# lcd_octopus_t2313.net
KiCad netlist of a schematic drawn in EAGLE
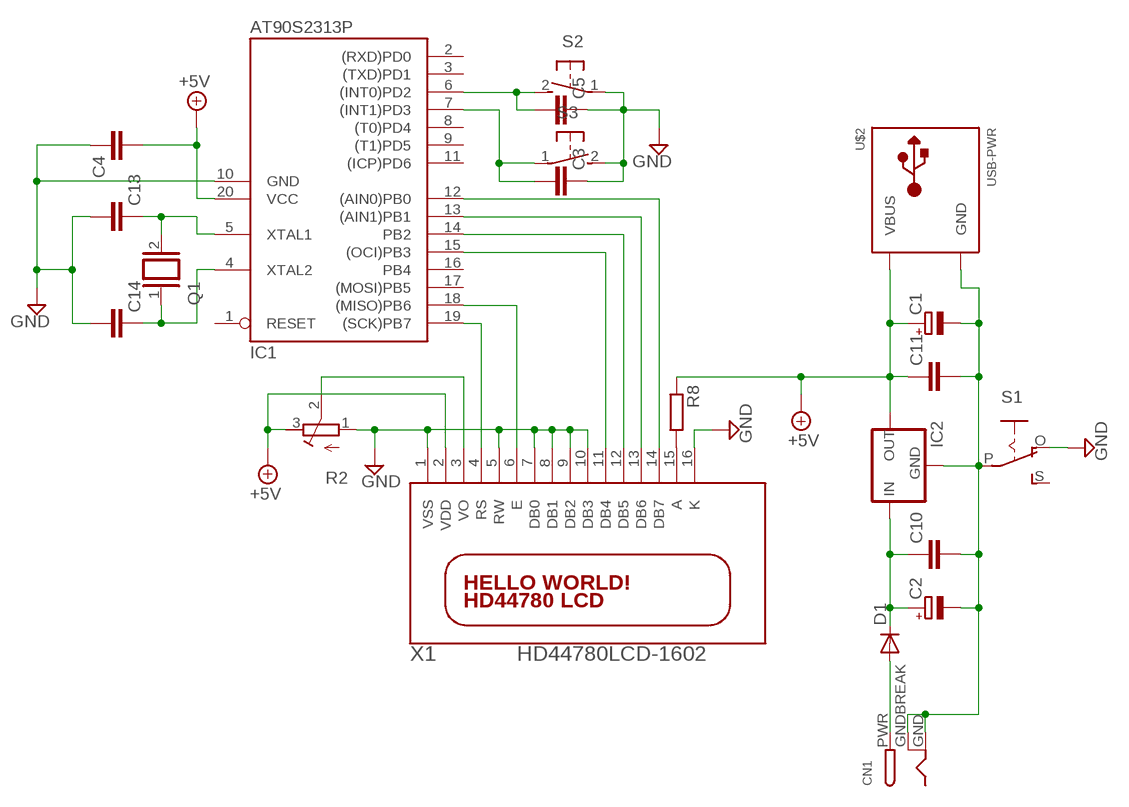
[diagram p0: schematic, sheet 1]

(export (version "E")
  (design (tool "Eeschema 10.0.6"))
  (components
    (comp (ref "C1")
      (value "CPOL-EUTT2D5L")
      (footprint "eagle-import:TT2D5L")
      (libsource (lib "eagle-import") (part "CPOL-EUTT2D5L"))
    )
    (comp (ref "C2")
      (value "CPOL-EUTT2D5L")
      (footprint "eagle-import:TT2D5L")
      (libsource (lib "eagle-import") (part "CPOL-EUTT2D5L"))
    )
    (comp (ref "C3")
      (value "C-EU025-025X050")
      (footprint "eagle-import:C025-025X050")
      (libsource (lib "eagle-import") (part "C-EU025-025X050"))
    )
    (comp (ref "C4")
      (value "C-EU025-025X050")
      (footprint "eagle-import:C025-025X050")
      (libsource (lib "eagle-import") (part "C-EU025-025X050"))
    )
    (comp (ref "C5")
      (value "C-EU025-025X050")
      (footprint "eagle-import:C025-025X050")
      (libsource (lib "eagle-import") (part "C-EU025-025X050"))
    )
    (comp (ref "C10")
      (value "C-EU025-025X050")
      (footprint "eagle-import:C025-025X050")
      (libsource (lib "eagle-import") (part "C-EU025-025X050"))
    )
    (comp (ref "C11")
      (value "C-EU025-025X050")
      (footprint "eagle-import:C025-025X050")
      (libsource (lib "eagle-import") (part "C-EU025-025X050"))
    )
    (comp (ref "C13")
      (value "C-EU025-025X050")
      (footprint "eagle-import:C025-025X050")
      (libsource (lib "eagle-import") (part "C-EU025-025X050"))
    )
    (comp (ref "C14")
      (value "C-EU025-025X050")
      (footprint "eagle-import:C025-025X050")
      (libsource (lib "eagle-import") (part "C-EU025-025X050"))
    )
    (comp (ref "CN1")
      (value "DCBARRELPTH")
      (footprint "eagle-import:DCJACK_2MM_PTH")
      (libsource (lib "eagle-import") (part "DCBARRELPTH"))
    )
    (comp (ref "D1")
      (value "DIODE-D-2.5")
      (footprint "eagle-import:D-2.5")
      (libsource (lib "eagle-import") (part "DIODE-D-2.5"))
    )
    (comp (ref "IC1")
      (value "AT90S2313P")
      (footprint "eagle-import:DIL20")
      (libsource (lib "eagle-import") (part "AT90S2313P"))
    )
    (comp (ref "IC2")
      (value "78XX_V")
      (footprint "eagle-import:78XXV")
      (libsource (lib "eagle-import") (part "78XX_V"))
    )
    (comp (ref "Q1")
      (value "XTAL/S")
      (footprint "eagle-import:QS")
      (libsource (lib "eagle-import") (part "XTAL/S"))
    )
    (comp (ref "R2")
      (value "R-TRIMM3339P")
      (footprint "eagle-import:RTRIM3339P")
      (libsource (lib "eagle-import") (part "R-TRIMM3339P"))
    )
    (comp (ref "R8")
      (value "R-EU_0207/10")
      (footprint "eagle-import:0207_10")
      (libsource (lib "eagle-import") (part "R-EU_0207/10"))
    )
    (comp (ref "S1")
      (value "EG1218S")
      (footprint "eagle-import:EG1218")
      (libsource (lib "eagle-import") (part "EG1218S"))
    )
    (comp (ref "S2")
      (value "31-XX")
      (footprint "eagle-import:B3F-31XX")
      (libsource (lib "eagle-import") (part "31-XX"))
    )
    (comp (ref "S3")
      (value "31-XX")
      (footprint "eagle-import:B3F-31XX")
      (libsource (lib "eagle-import") (part "31-XX"))
    )
    (comp (ref "U$2")
      (value "USB-PWR")
      (footprint "eagle-import:USB-MINIB-THM-MOLEX-PWRONLY")
      (libsource (lib "eagle-import") (part "USB-PWR"))
    )
    (comp (ref "X1")
      (value "HD44780LCD-1602")
      (footprint "eagle-import:LCD1602")
      (libsource (lib "eagle-import") (part "HD44780LCD-1602"))
    )
  )
  (nets
    (net (code "1") (name "+5V") (class "Default")
      (node (ref "C1") (pin "+") (pinfunction "+_+") (pintype "passive"))
      (node (ref "C11") (pin "1") (pinfunction "1_1") (pintype "passive"))
      (node (ref "C4") (pin "2") (pinfunction "2_2") (pintype "passive"))
      (node (ref "IC1") (pin "20") (pinfunction "VCC_20") (pintype "power_in"))
      (node (ref "IC2") (pin "OUT") (pinfunction "OUT_OUT") (pintype "passive"))
      (node (ref "R2") (pin "3") (pinfunction "E_3") (pintype "passive"))
      (node (ref "R8") (pin "1") (pinfunction "1_1") (pintype "passive"))
      (node (ref "U$2") (pin "VBUS") (pinfunction "VBUS_VBUS") (pintype "power_in"))
      (node (ref "X1") (pin "2") (pinfunction "VDD_2") (pintype "power_in"))
    )
    (net (code "2") (name "GND") (class "Default")
      (node (ref "C13") (pin "2") (pinfunction "2_2") (pintype "passive"))
      (node (ref "C14") (pin "2") (pinfunction "2_2") (pintype "passive"))
      (node (ref "C3") (pin "1") (pinfunction "1_1") (pintype "passive"))
      (node (ref "C4") (pin "1") (pinfunction "1_1") (pintype "passive"))
      (node (ref "C5") (pin "1") (pinfunction "1_1") (pintype "passive"))
      (node (ref "IC1") (pin "10") (pinfunction "GND_10") (pintype "power_in"))
      (node (ref "R2") (pin "1") (pinfunction "A_1") (pintype "passive"))
      (node (ref "S1") (pin "O") (pinfunction "O_O") (pintype "passive"))
      (node (ref "S2") (pin "1") (pinfunction "P_1") (pintype "passive"))
      (node (ref "S3") (pin "2") (pinfunction "S_2") (pintype "passive"))
      (node (ref "X1") (pin "1") (pinfunction "VSS_1") (pintype "power_in"))
      (node (ref "X1") (pin "10") (pinfunction "DB3_10") (pintype "bidirectional"))
      (node (ref "X1") (pin "16") (pinfunction "K_16") (pintype "input"))
      (node (ref "X1") (pin "5") (pinfunction "RW_5") (pintype "input"))
      (node (ref "X1") (pin "7") (pinfunction "DB0_7") (pintype "bidirectional"))
      (node (ref "X1") (pin "8") (pinfunction "DB1_8") (pintype "bidirectional"))
      (node (ref "X1") (pin "9") (pinfunction "DB2_9") (pintype "bidirectional"))
    )
    (net (code "3") (name "Net-(C1-Pad-)") (class "Default")
      (node (ref "C1") (pin "-") (pinfunction "-_-") (pintype "passive"))
      (node (ref "C10") (pin "2") (pinfunction "2_2") (pintype "passive"))
      (node (ref "C11") (pin "2") (pinfunction "2_2") (pintype "passive"))
      (node (ref "C2") (pin "-") (pinfunction "-_-") (pintype "passive"))
      (node (ref "CN1") (pin "GND") (pinfunction "GND_GND") (pintype "power_in"))
      (node (ref "CN1") (pin "GNDBREAK") (pinfunction "GNDBREAK_GNDBREAK") (pintype "power_in"))
      (node (ref "IC2") (pin "GND") (pinfunction "GND_GND") (pintype "input"))
      (node (ref "S1") (pin "P") (pinfunction "P_P") (pintype "passive"))
      (node (ref "U$2") (pin "GND") (pinfunction "GND_GND") (pintype "power_in"))
    )
    (net (code "4") (name "Net-(C10-Pad1)") (class "Default")
      (node (ref "C10") (pin "1") (pinfunction "1_1") (pintype "passive"))
      (node (ref "C2") (pin "+") (pinfunction "+_+") (pintype "passive"))
      (node (ref "D1") (pin "C") (pinfunction "C_C") (pintype "passive"))
      (node (ref "IC2") (pin "IN") (pinfunction "IN_IN") (pintype "input"))
    )
    (net (code "5") (name "Net-(CN1-PadPWR)") (class "Default")
      (node (ref "CN1") (pin "PWR") (pinfunction "PWR_PWR") (pintype "power_in"))
      (node (ref "D1") (pin "A") (pinfunction "A_A") (pintype "passive"))
    )
    (net (code "6") (name "Net-(IC1-(AIN0)PB0)") (class "Default")
      (node (ref "IC1") (pin "12") (pinfunction "(AIN0)PB0_12") (pintype "bidirectional"))
      (node (ref "X1") (pin "14") (pinfunction "DB7_14") (pintype "bidirectional"))
    )
    (net (code "7") (name "Net-(IC1-(AIN1)PB1)") (class "Default")
      (node (ref "IC1") (pin "13") (pinfunction "(AIN1)PB1_13") (pintype "bidirectional"))
      (node (ref "X1") (pin "13") (pinfunction "DB6_13") (pintype "bidirectional"))
    )
    (net (code "8") (name "Net-(IC1-(INT0)PD2)") (class "Default")
      (node (ref "C5") (pin "2") (pinfunction "2_2") (pintype "passive"))
      (node (ref "IC1") (pin "6") (pinfunction "(INT0)PD2_6") (pintype "bidirectional"))
      (node (ref "S2") (pin "2") (pinfunction "S_2") (pintype "passive"))
    )
    (net (code "9") (name "Net-(IC1-(INT1)PD3)") (class "Default")
      (node (ref "C3") (pin "2") (pinfunction "2_2") (pintype "passive"))
      (node (ref "IC1") (pin "7") (pinfunction "(INT1)PD3_7") (pintype "bidirectional"))
      (node (ref "S3") (pin "1") (pinfunction "P_1") (pintype "passive"))
    )
    (net (code "10") (name "Net-(IC1-(MISO)PB6)") (class "Default")
      (node (ref "IC1") (pin "18") (pinfunction "(MISO)PB6_18") (pintype "bidirectional"))
      (node (ref "X1") (pin "6") (pinfunction "E_6") (pintype "input"))
    )
    (net (code "11") (name "Net-(IC1-(OCI)PB3)") (class "Default")
      (node (ref "IC1") (pin "15") (pinfunction "(OCI)PB3_15") (pintype "bidirectional"))
      (node (ref "X1") (pin "11") (pinfunction "DB4_11") (pintype "bidirectional"))
    )
    (net (code "12") (name "Net-(IC1-(SCK)PB7)") (class "Default")
      (node (ref "IC1") (pin "19") (pinfunction "(SCK)PB7_19") (pintype "bidirectional"))
      (node (ref "X1") (pin "4") (pinfunction "RS_4") (pintype "input"))
    )
    (net (code "13") (name "Net-(IC1-PB2)") (class "Default")
      (node (ref "IC1") (pin "14") (pinfunction "PB2_14") (pintype "bidirectional"))
      (node (ref "X1") (pin "12") (pinfunction "DB5_12") (pintype "bidirectional"))
    )
    (net (code "14") (name "Net-(IC1-XTAL1)") (class "Default")
      (node (ref "C13") (pin "1") (pinfunction "1_1") (pintype "passive"))
      (node (ref "IC1") (pin "5") (pinfunction "XTAL1_5") (pintype "bidirectional"))
      (node (ref "Q1") (pin "2") (pinfunction "2_2") (pintype "passive"))
    )
    (net (code "15") (name "Net-(IC1-XTAL2)") (class "Default")
      (node (ref "C14") (pin "1") (pinfunction "1_1") (pintype "passive"))
      (node (ref "IC1") (pin "4") (pinfunction "XTAL2_4") (pintype "bidirectional"))
      (node (ref "Q1") (pin "1") (pinfunction "1_1") (pintype "passive"))
    )
    (net (code "16") (name "Net-(R2-S)") (class "Default")
      (node (ref "R2") (pin "2") (pinfunction "S_2") (pintype "passive"))
      (node (ref "X1") (pin "3") (pinfunction "VO_3") (pintype "input"))
    )
    (net (code "17") (name "Net-(X1-A)") (class "Default")
      (node (ref "R8") (pin "2") (pinfunction "2_2") (pintype "passive"))
      (node (ref "X1") (pin "15") (pinfunction "A_15") (pintype "input"))
    )
    (net (code "18") (name "unconnected-(IC1-(ICP)PD6-Pad11)") (class "Default")
      (node (ref "IC1") (pin "11") (pinfunction "(ICP)PD6_11") (pintype "bidirectional"))
    )
    (net (code "19") (name "unconnected-(IC1-(MOSI)PB5-Pad17)") (class "Default")
      (node (ref "IC1") (pin "17") (pinfunction "(MOSI)PB5_17") (pintype "bidirectional"))
    )
    (net (code "20") (name "unconnected-(IC1-(RXD)PD0-Pad2)") (class "Default")
      (node (ref "IC1") (pin "2") (pinfunction "(RXD)PD0_2") (pintype "bidirectional"))
    )
    (net (code "21") (name "unconnected-(IC1-(T0)PD4-Pad8)") (class "Default")
      (node (ref "IC1") (pin "8") (pinfunction "(T0)PD4_8") (pintype "bidirectional"))
    )
    (net (code "22") (name "unconnected-(IC1-(T1)PD5-Pad9)") (class "Default")
      (node (ref "IC1") (pin "9") (pinfunction "(T1)PD5_9") (pintype "bidirectional"))
    )
    (net (code "23") (name "unconnected-(IC1-(TXD)PD1-Pad3)") (class "Default")
      (node (ref "IC1") (pin "3") (pinfunction "(TXD)PD1_3") (pintype "bidirectional"))
    )
    (net (code "24") (name "unconnected-(IC1-PB4-Pad16)") (class "Default")
      (node (ref "IC1") (pin "16") (pinfunction "PB4_16") (pintype "bidirectional"))
    )
    (net (code "25") (name "unconnected-(IC1-RESET-Pad1)") (class "Default")
      (node (ref "IC1") (pin "1") (pinfunction "RESET_1") (pintype "bidirectional"))
    )
    (net (code "26") (name "unconnected-(S1-PadS)") (class "Default")
      (node (ref "S1") (pin "S") (pinfunction "S_S") (pintype "passive"))
    )
  )
)
